# transceiver_434MHz_v1.net
KiCad netlist of a schematic drawn in EAGLE
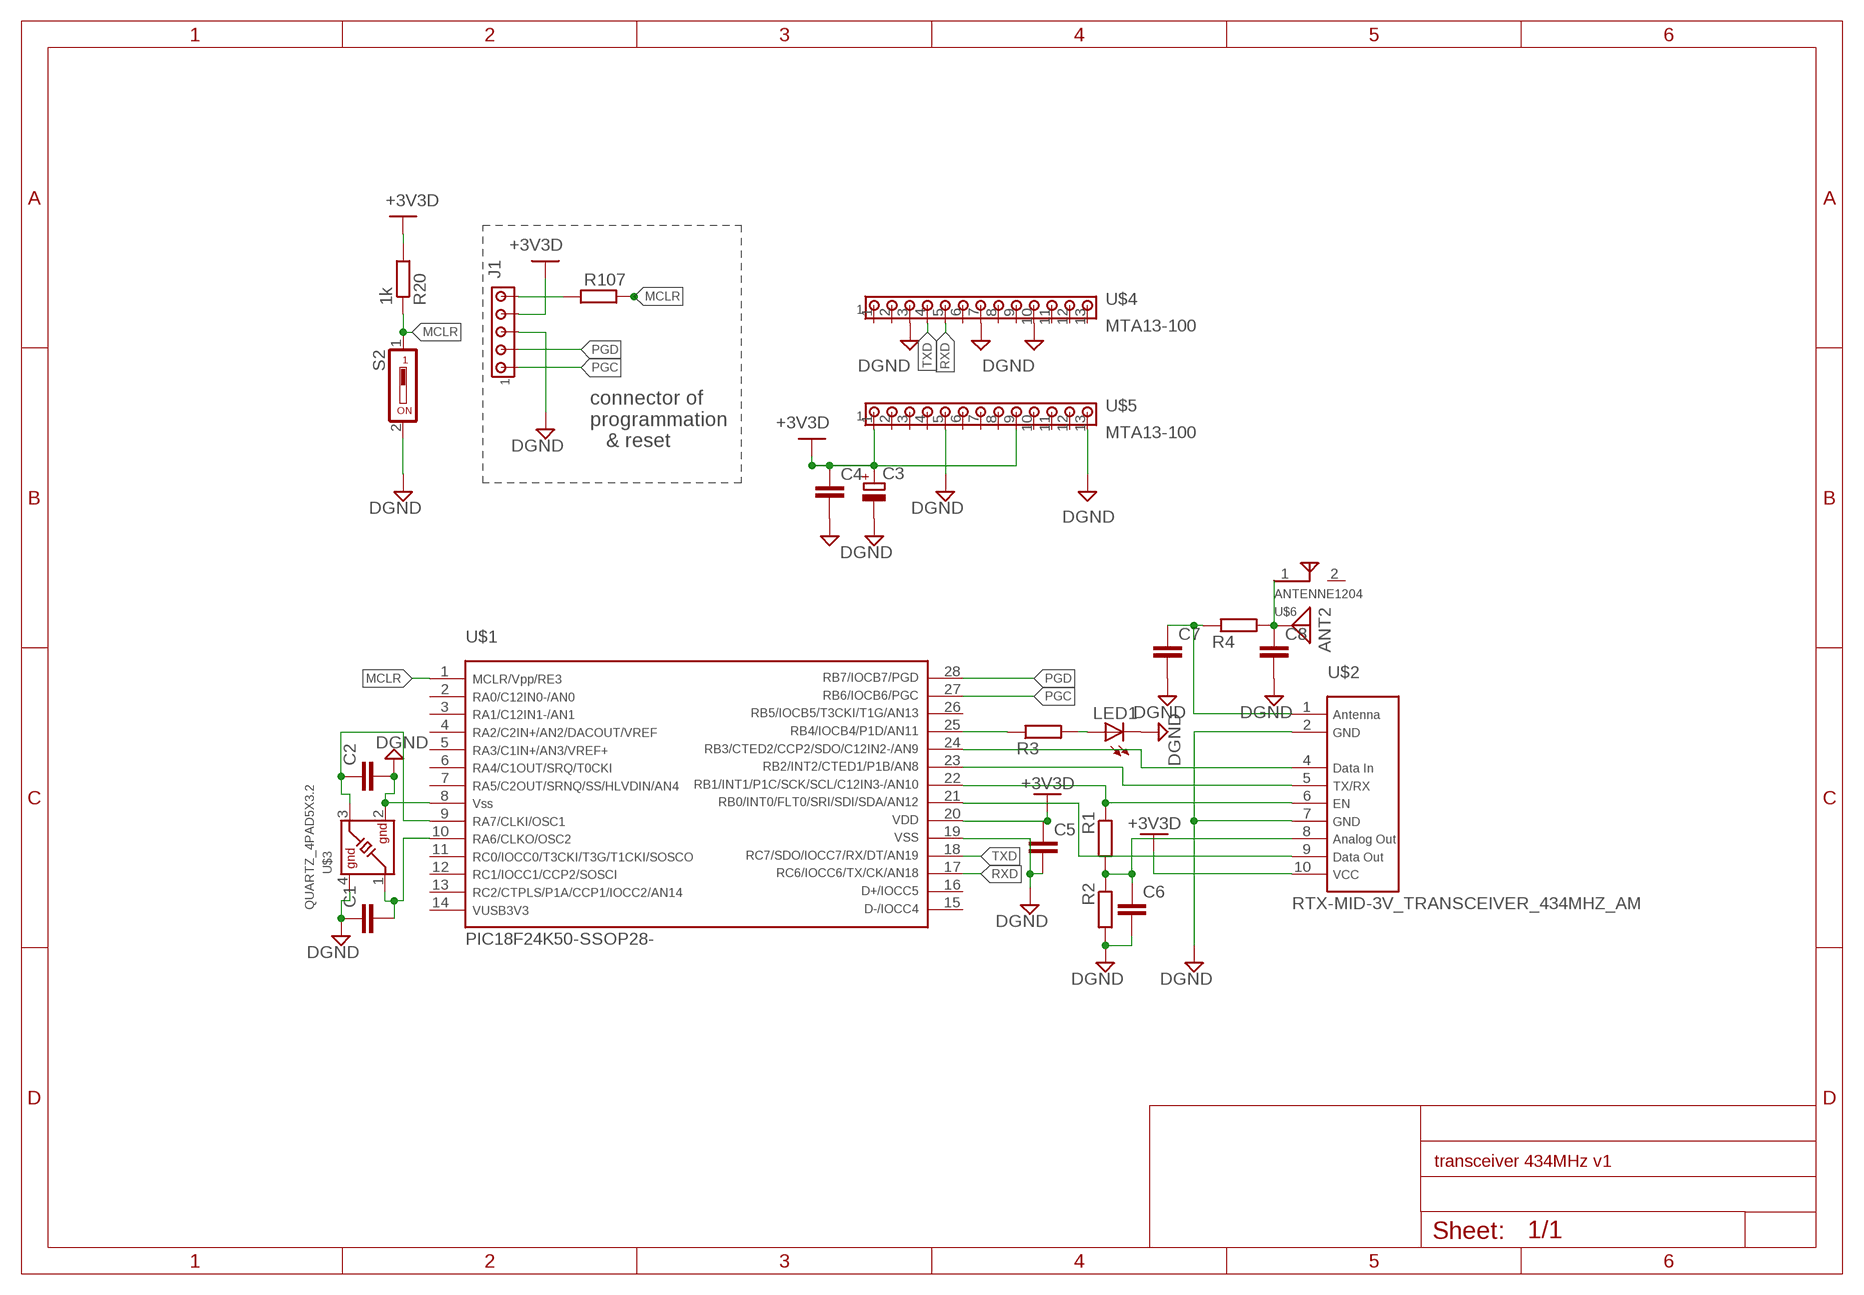
[diagram p0: schematic, sheet 1]

(export (version "E")
  (design (tool "Eeschema 10.0.6"))
  (components
    (comp (ref "ANT2")
      (value "ANTENNA")
      (footprint "eagle-import:PAD-01")
      (libsource (lib "eagle-import") (part "ANTENNA"))
    )
    (comp (ref "C1")
      (value "C-EUC0805")
      (footprint "eagle-import:C0805")
      (libsource (lib "eagle-import") (part "C-EUC0805"))
    )
    (comp (ref "C2")
      (value "C-EUC0805")
      (footprint "eagle-import:C0805")
      (libsource (lib "eagle-import") (part "C-EUC0805"))
    )
    (comp (ref "C3")
      (value "CPOL-EUSMCB")
      (footprint "eagle-import:SMC_B")
      (libsource (lib "eagle-import") (part "CPOL-EUSMCB"))
    )
    (comp (ref "C4")
      (value "C-EUC0805")
      (footprint "eagle-import:C0805")
      (libsource (lib "eagle-import") (part "C-EUC0805"))
    )
    (comp (ref "C5")
      (value "C-EUC0805")
      (footprint "eagle-import:C0805")
      (libsource (lib "eagle-import") (part "C-EUC0805"))
    )
    (comp (ref "C6")
      (value "C-EUC0805")
      (footprint "eagle-import:C0805")
      (libsource (lib "eagle-import") (part "C-EUC0805"))
    )
    (comp (ref "C7")
      (value "C-EUC0805")
      (footprint "eagle-import:C0805")
      (libsource (lib "eagle-import") (part "C-EUC0805"))
    )
    (comp (ref "C8")
      (value "C-EUC0805")
      (footprint "eagle-import:C0805")
      (libsource (lib "eagle-import") (part "C-EUC0805"))
    )
    (comp (ref "J1")
      (value "MTA05-100")
      (footprint "eagle-import:10X05MTA")
      (libsource (lib "eagle-import") (part "MTA05-100"))
    )
    (comp (ref "LED1")
      (value "LEDCHIPLED_0805")
      (footprint "eagle-import:CHIPLED_0805")
      (libsource (lib "eagle-import") (part "LEDCHIPLED_0805"))
    )
    (comp (ref "R1")
      (value "R-EU_R0805")
      (footprint "eagle-import:R0805")
      (libsource (lib "eagle-import") (part "R-EU_R0805"))
    )
    (comp (ref "R2")
      (value "R-EU_R0805")
      (footprint "eagle-import:R0805")
      (libsource (lib "eagle-import") (part "R-EU_R0805"))
    )
    (comp (ref "R3")
      (value "R-EU_R0805")
      (footprint "eagle-import:R0805")
      (libsource (lib "eagle-import") (part "R-EU_R0805"))
    )
    (comp (ref "R4")
      (value "R-EU_R0805")
      (footprint "eagle-import:R0805")
      (libsource (lib "eagle-import") (part "R-EU_R0805"))
    )
    (comp (ref "R20")
      (value "1k")
      (footprint "eagle-import:R0805")
      (libsource (lib "eagle-import") (part "R-EU_R0805"))
    )
    (comp (ref "R107")
      (value "R-EU_R0805")
      (footprint "eagle-import:R0805")
      (libsource (lib "eagle-import") (part "R-EU_R0805"))
    )
    (comp (ref "S2")
      (value "DS01")
      (footprint "eagle-import:DS-01")
      (libsource (lib "eagle-import") (part "DS01"))
    )
    (comp (ref "U$1")
      (value "PIC18F24K50-SSOP28-")
      (footprint "eagle-import:SOP254P785X200-28N")
      (libsource (lib "eagle-import") (part "PIC18F24K50-SSOP28-"))
    )
    (comp (ref "U$2")
      (value "RTX-MID-3V_TRANSCEIVER_434MHZ_AM")
      (footprint "eagle-import:TRASCEIVER-434MHZ_AM")
      (libsource (lib "eagle-import") (part "RTX-MID-3V_TRANSCEIVER_434MHZ_AM"))
    )
    (comp (ref "U$3")
      (value "QUARTZ_4PAD5X3.2")
      (footprint "eagle-import:OSC_5X3.2")
      (libsource (lib "eagle-import") (part "QUARTZ_4PAD5X3.2"))
    )
    (comp (ref "U$4")
      (value "MTA13-100")
      (footprint "eagle-import:10X13MTA")
      (libsource (lib "eagle-import") (part "MTA13-100"))
    )
    (comp (ref "U$5")
      (value "MTA13-100")
      (footprint "eagle-import:10X13MTA")
      (libsource (lib "eagle-import") (part "MTA13-100"))
    )
    (comp (ref "U$6")
      (value "ANTENNE1204")
      (footprint "eagle-import:ANTENNE1204")
      (libsource (lib "eagle-import") (part "ANTENNE1204"))
    )
  )
  (nets
    (net (code "1") (name "+3V3D") (class "Default")
      (node (ref "C3") (pin "+") (pinfunction "+_+") (pintype "passive"))
      (node (ref "C4") (pin "1") (pinfunction "1_1") (pintype "passive"))
      (node (ref "C5") (pin "1") (pinfunction "1_1") (pintype "passive"))
      (node (ref "J1") (pin "4") (pinfunction "4_4") (pintype "passive"))
      (node (ref "R20") (pin "2") (pinfunction "2_2") (pintype "passive"))
      (node (ref "U$1") (pin "20") (pinfunction "P$20_20") (pintype "bidirectional"))
      (node (ref "U$2") (pin "10") (pinfunction "10_10") (pintype "bidirectional"))
      (node (ref "U$5") (pin "1") (pinfunction "1_1") (pintype "passive"))
      (node (ref "U$5") (pin "9") (pinfunction "9_9") (pintype "passive"))
    )
    (net (code "2") (name "DGND") (class "Default")
      (node (ref "C1") (pin "1") (pinfunction "1_1") (pintype "passive"))
      (node (ref "C2") (pin "2") (pinfunction "2_2") (pintype "passive"))
      (node (ref "C3") (pin "-") (pinfunction "-_-") (pintype "passive"))
      (node (ref "C4") (pin "2") (pinfunction "2_2") (pintype "passive"))
      (node (ref "C5") (pin "2") (pinfunction "2_2") (pintype "passive"))
      (node (ref "C6") (pin "2") (pinfunction "2_2") (pintype "passive"))
      (node (ref "C7") (pin "2") (pinfunction "2_2") (pintype "passive"))
      (node (ref "C8") (pin "2") (pinfunction "2_2") (pintype "passive"))
      (node (ref "J1") (pin "3") (pinfunction "3_3") (pintype "passive"))
      (node (ref "LED1") (pin "C") (pinfunction "C_C") (pintype "passive"))
      (node (ref "R2") (pin "2") (pinfunction "2_2") (pintype "passive"))
      (node (ref "S2") (pin "2") (pinfunction "2_2") (pintype "passive"))
      (node (ref "U$1") (pin "19") (pinfunction "P$19_19") (pintype "bidirectional"))
      (node (ref "U$1") (pin "8") (pinfunction "P$8_8") (pintype "bidirectional"))
      (node (ref "U$2") (pin "2") (pinfunction "2_2") (pintype "bidirectional"))
      (node (ref "U$2") (pin "7") (pinfunction "7_7") (pintype "bidirectional"))
      (node (ref "U$3") (pin "2") (pinfunction "2_2") (pintype "bidirectional"))
      (node (ref "U$3") (pin "4") (pinfunction "4_4") (pintype "bidirectional"))
      (node (ref "U$4") (pin "10") (pinfunction "10_10") (pintype "passive"))
      (node (ref "U$4") (pin "3") (pinfunction "3_3") (pintype "passive"))
      (node (ref "U$4") (pin "7") (pinfunction "7_7") (pintype "passive"))
      (node (ref "U$5") (pin "13") (pinfunction "13_13") (pintype "passive"))
      (node (ref "U$5") (pin "5") (pinfunction "5_5") (pintype "passive"))
    )
    (net (code "3") (name "MCLR") (class "Default")
      (node (ref "R107") (pin "1") (pinfunction "1_1") (pintype "passive"))
      (node (ref "R20") (pin "1") (pinfunction "1_1") (pintype "passive"))
      (node (ref "S2") (pin "1") (pinfunction "1_1") (pintype "passive"))
      (node (ref "U$1") (pin "1") (pinfunction "P$1_1") (pintype "bidirectional"))
    )
    (net (code "4") (name "Net-(C6-Pad1)") (class "Default")
      (node (ref "C6") (pin "1") (pinfunction "1_1") (pintype "passive"))
      (node (ref "R1") (pin "2") (pinfunction "2_2") (pintype "passive"))
      (node (ref "R2") (pin "1") (pinfunction "1_1") (pintype "passive"))
      (node (ref "U$2") (pin "8") (pinfunction "8_8") (pintype "bidirectional"))
    )
    (net (code "5") (name "Net-(C7-Pad1)") (class "Default")
      (node (ref "C7") (pin "1") (pinfunction "1_1") (pintype "passive"))
      (node (ref "R4") (pin "1") (pinfunction "1_1") (pintype "passive"))
      (node (ref "U$2") (pin "1") (pinfunction "1_1") (pintype "bidirectional"))
    )
    (net (code "6") (name "Net-(J1-Pad5)") (class "Default")
      (node (ref "J1") (pin "5") (pinfunction "5_5") (pintype "passive"))
      (node (ref "R107") (pin "2") (pinfunction "2_2") (pintype "passive"))
    )
    (net (code "7") (name "Net-(LED1-PadA)") (class "Default")
      (node (ref "LED1") (pin "A") (pinfunction "A_A") (pintype "passive"))
      (node (ref "R3") (pin "2") (pinfunction "2_2") (pintype "passive"))
    )
    (net (code "8") (name "Net-(U$1-P$9)") (class "Default")
      (node (ref "C2") (pin "1") (pinfunction "1_1") (pintype "passive"))
      (node (ref "U$1") (pin "9") (pinfunction "P$9_9") (pintype "bidirectional"))
      (node (ref "U$3") (pin "3") (pinfunction "3_3") (pintype "bidirectional"))
    )
    (net (code "9") (name "Net-(U$1-P$10)") (class "Default")
      (node (ref "C1") (pin "2") (pinfunction "2_2") (pintype "passive"))
      (node (ref "U$1") (pin "10") (pinfunction "P$10_10") (pintype "bidirectional"))
      (node (ref "U$3") (pin "1") (pinfunction "1_1") (pintype "bidirectional"))
    )
    (net (code "10") (name "Net-(U$1-P$21)") (class "Default")
      (node (ref "U$1") (pin "21") (pinfunction "P$21_21") (pintype "bidirectional"))
      (node (ref "U$2") (pin "9") (pinfunction "9_9") (pintype "bidirectional"))
    )
    (net (code "11") (name "Net-(U$1-P$22)") (class "Default")
      (node (ref "R1") (pin "1") (pinfunction "1_1") (pintype "passive"))
      (node (ref "U$1") (pin "22") (pinfunction "P$22_22") (pintype "bidirectional"))
      (node (ref "U$2") (pin "6") (pinfunction "6_6") (pintype "bidirectional"))
    )
    (net (code "12") (name "Net-(U$1-P$23)") (class "Default")
      (node (ref "U$1") (pin "23") (pinfunction "P$23_23") (pintype "bidirectional"))
      (node (ref "U$2") (pin "5") (pinfunction "5_5") (pintype "bidirectional"))
    )
    (net (code "13") (name "Net-(U$1-P$24)") (class "Default")
      (node (ref "U$1") (pin "24") (pinfunction "P$24_24") (pintype "bidirectional"))
      (node (ref "U$2") (pin "4") (pinfunction "4_4") (pintype "bidirectional"))
    )
    (net (code "14") (name "Net-(U$1-P$25)") (class "Default")
      (node (ref "R3") (pin "1") (pinfunction "1_1") (pintype "passive"))
      (node (ref "U$1") (pin "25") (pinfunction "P$25_25") (pintype "bidirectional"))
    )
    (net (code "15") (name "Net-(U$6-P$1)") (class "Default")
      (node (ref "ANT2") (pin "1") (pinfunction "1_1") (pintype "output"))
      (node (ref "C8") (pin "1") (pinfunction "1_1") (pintype "passive"))
      (node (ref "R4") (pin "2") (pinfunction "2_2") (pintype "passive"))
      (node (ref "U$6") (pin "1") (pinfunction "P$1_1") (pintype "bidirectional"))
    )
    (net (code "16") (name "PGC") (class "Default")
      (node (ref "J1") (pin "1") (pinfunction "1_1") (pintype "passive"))
      (node (ref "U$1") (pin "27") (pinfunction "P$27_27") (pintype "bidirectional"))
    )
    (net (code "17") (name "PGD") (class "Default")
      (node (ref "J1") (pin "2") (pinfunction "2_2") (pintype "passive"))
      (node (ref "U$1") (pin "28") (pinfunction "P$28_28") (pintype "bidirectional"))
    )
    (net (code "18") (name "RXD") (class "Default")
      (node (ref "U$1") (pin "17") (pinfunction "P$17_17") (pintype "bidirectional"))
      (node (ref "U$4") (pin "5") (pinfunction "5_5") (pintype "passive"))
    )
    (net (code "19") (name "TXD") (class "Default")
      (node (ref "U$1") (pin "18") (pinfunction "P$18_18") (pintype "bidirectional"))
      (node (ref "U$4") (pin "4") (pinfunction "4_4") (pintype "passive"))
    )
    (net (code "20") (name "unconnected-(U$1-P$2-Pad2)") (class "Default")
      (node (ref "U$1") (pin "2") (pinfunction "P$2_2") (pintype "bidirectional"))
    )
    (net (code "21") (name "unconnected-(U$1-P$3-Pad3)") (class "Default")
      (node (ref "U$1") (pin "3") (pinfunction "P$3_3") (pintype "bidirectional"))
    )
    (net (code "22") (name "unconnected-(U$1-P$4-Pad4)") (class "Default")
      (node (ref "U$1") (pin "4") (pinfunction "P$4_4") (pintype "bidirectional"))
    )
    (net (code "23") (name "unconnected-(U$1-P$5-Pad5)") (class "Default")
      (node (ref "U$1") (pin "5") (pinfunction "P$5_5") (pintype "bidirectional"))
    )
    (net (code "24") (name "unconnected-(U$1-P$6-Pad6)") (class "Default")
      (node (ref "U$1") (pin "6") (pinfunction "P$6_6") (pintype "bidirectional"))
    )
    (net (code "25") (name "unconnected-(U$1-P$7-Pad7)") (class "Default")
      (node (ref "U$1") (pin "7") (pinfunction "P$7_7") (pintype "bidirectional"))
    )
    (net (code "26") (name "unconnected-(U$1-P$11-Pad11)") (class "Default")
      (node (ref "U$1") (pin "11") (pinfunction "P$11_11") (pintype "bidirectional"))
    )
    (net (code "27") (name "unconnected-(U$1-P$12-Pad12)") (class "Default")
      (node (ref "U$1") (pin "12") (pinfunction "P$12_12") (pintype "bidirectional"))
    )
    (net (code "28") (name "unconnected-(U$1-P$13-Pad13)") (class "Default")
      (node (ref "U$1") (pin "13") (pinfunction "P$13_13") (pintype "bidirectional"))
    )
    (net (code "29") (name "unconnected-(U$1-P$14-Pad14)") (class "Default")
      (node (ref "U$1") (pin "14") (pinfunction "P$14_14") (pintype "bidirectional"))
    )
    (net (code "30") (name "unconnected-(U$1-P$15-Pad15)") (class "Default")
      (node (ref "U$1") (pin "15") (pinfunction "P$15_15") (pintype "bidirectional"))
    )
    (net (code "31") (name "unconnected-(U$1-P$16-Pad16)") (class "Default")
      (node (ref "U$1") (pin "16") (pinfunction "P$16_16") (pintype "bidirectional"))
    )
    (net (code "32") (name "unconnected-(U$1-P$26-Pad26)") (class "Default")
      (node (ref "U$1") (pin "26") (pinfunction "P$26_26") (pintype "bidirectional"))
    )
    (net (code "33") (name "unconnected-(U$4-Pad1)") (class "Default")
      (node (ref "U$4") (pin "1") (pinfunction "1_1") (pintype "passive"))
    )
    (net (code "34") (name "unconnected-(U$4-Pad2)") (class "Default")
      (node (ref "U$4") (pin "2") (pinfunction "2_2") (pintype "passive"))
    )
    (net (code "35") (name "unconnected-(U$4-Pad6)") (class "Default")
      (node (ref "U$4") (pin "6") (pinfunction "6_6") (pintype "passive"))
    )
    (net (code "36") (name "unconnected-(U$4-Pad8)") (class "Default")
      (node (ref "U$4") (pin "8") (pinfunction "8_8") (pintype "passive"))
    )
    (net (code "37") (name "unconnected-(U$4-Pad9)") (class "Default")
      (node (ref "U$4") (pin "9") (pinfunction "9_9") (pintype "passive"))
    )
    (net (code "38") (name "unconnected-(U$4-Pad11)") (class "Default")
      (node (ref "U$4") (pin "11") (pinfunction "11_11") (pintype "passive"))
    )
    (net (code "39") (name "unconnected-(U$4-Pad12)") (class "Default")
      (node (ref "U$4") (pin "12") (pinfunction "12_12") (pintype "passive"))
    )
    (net (code "40") (name "unconnected-(U$4-Pad13)") (class "Default")
      (node (ref "U$4") (pin "13") (pinfunction "13_13") (pintype "passive"))
    )
    (net (code "41") (name "unconnected-(U$5-Pad2)") (class "Default")
      (node (ref "U$5") (pin "2") (pinfunction "2_2") (pintype "passive"))
    )
    (net (code "42") (name "unconnected-(U$5-Pad3)") (class "Default")
      (node (ref "U$5") (pin "3") (pinfunction "3_3") (pintype "passive"))
    )
    (net (code "43") (name "unconnected-(U$5-Pad4)") (class "Default")
      (node (ref "U$5") (pin "4") (pinfunction "4_4") (pintype "passive"))
    )
    (net (code "44") (name "unconnected-(U$5-Pad6)") (class "Default")
      (node (ref "U$5") (pin "6") (pinfunction "6_6") (pintype "passive"))
    )
    (net (code "45") (name "unconnected-(U$5-Pad7)") (class "Default")
      (node (ref "U$5") (pin "7") (pinfunction "7_7") (pintype "passive"))
    )
    (net (code "46") (name "unconnected-(U$5-Pad8)") (class "Default")
      (node (ref "U$5") (pin "8") (pinfunction "8_8") (pintype "passive"))
    )
    (net (code "47") (name "unconnected-(U$5-Pad10)") (class "Default")
      (node (ref "U$5") (pin "10") (pinfunction "10_10") (pintype "passive"))
    )
    (net (code "48") (name "unconnected-(U$5-Pad11)") (class "Default")
      (node (ref "U$5") (pin "11") (pinfunction "11_11") (pintype "passive"))
    )
    (net (code "49") (name "unconnected-(U$5-Pad12)") (class "Default")
      (node (ref "U$5") (pin "12") (pinfunction "12_12") (pintype "passive"))
    )
    (net (code "50") (name "unconnected-(U$6-P$2-Pad2)") (class "Default")
      (node (ref "U$6") (pin "2") (pinfunction "P$2_2") (pintype "bidirectional"))
    )
  )
)
